# Impedance.net
KiCad netlist of a schematic drawn in EAGLE
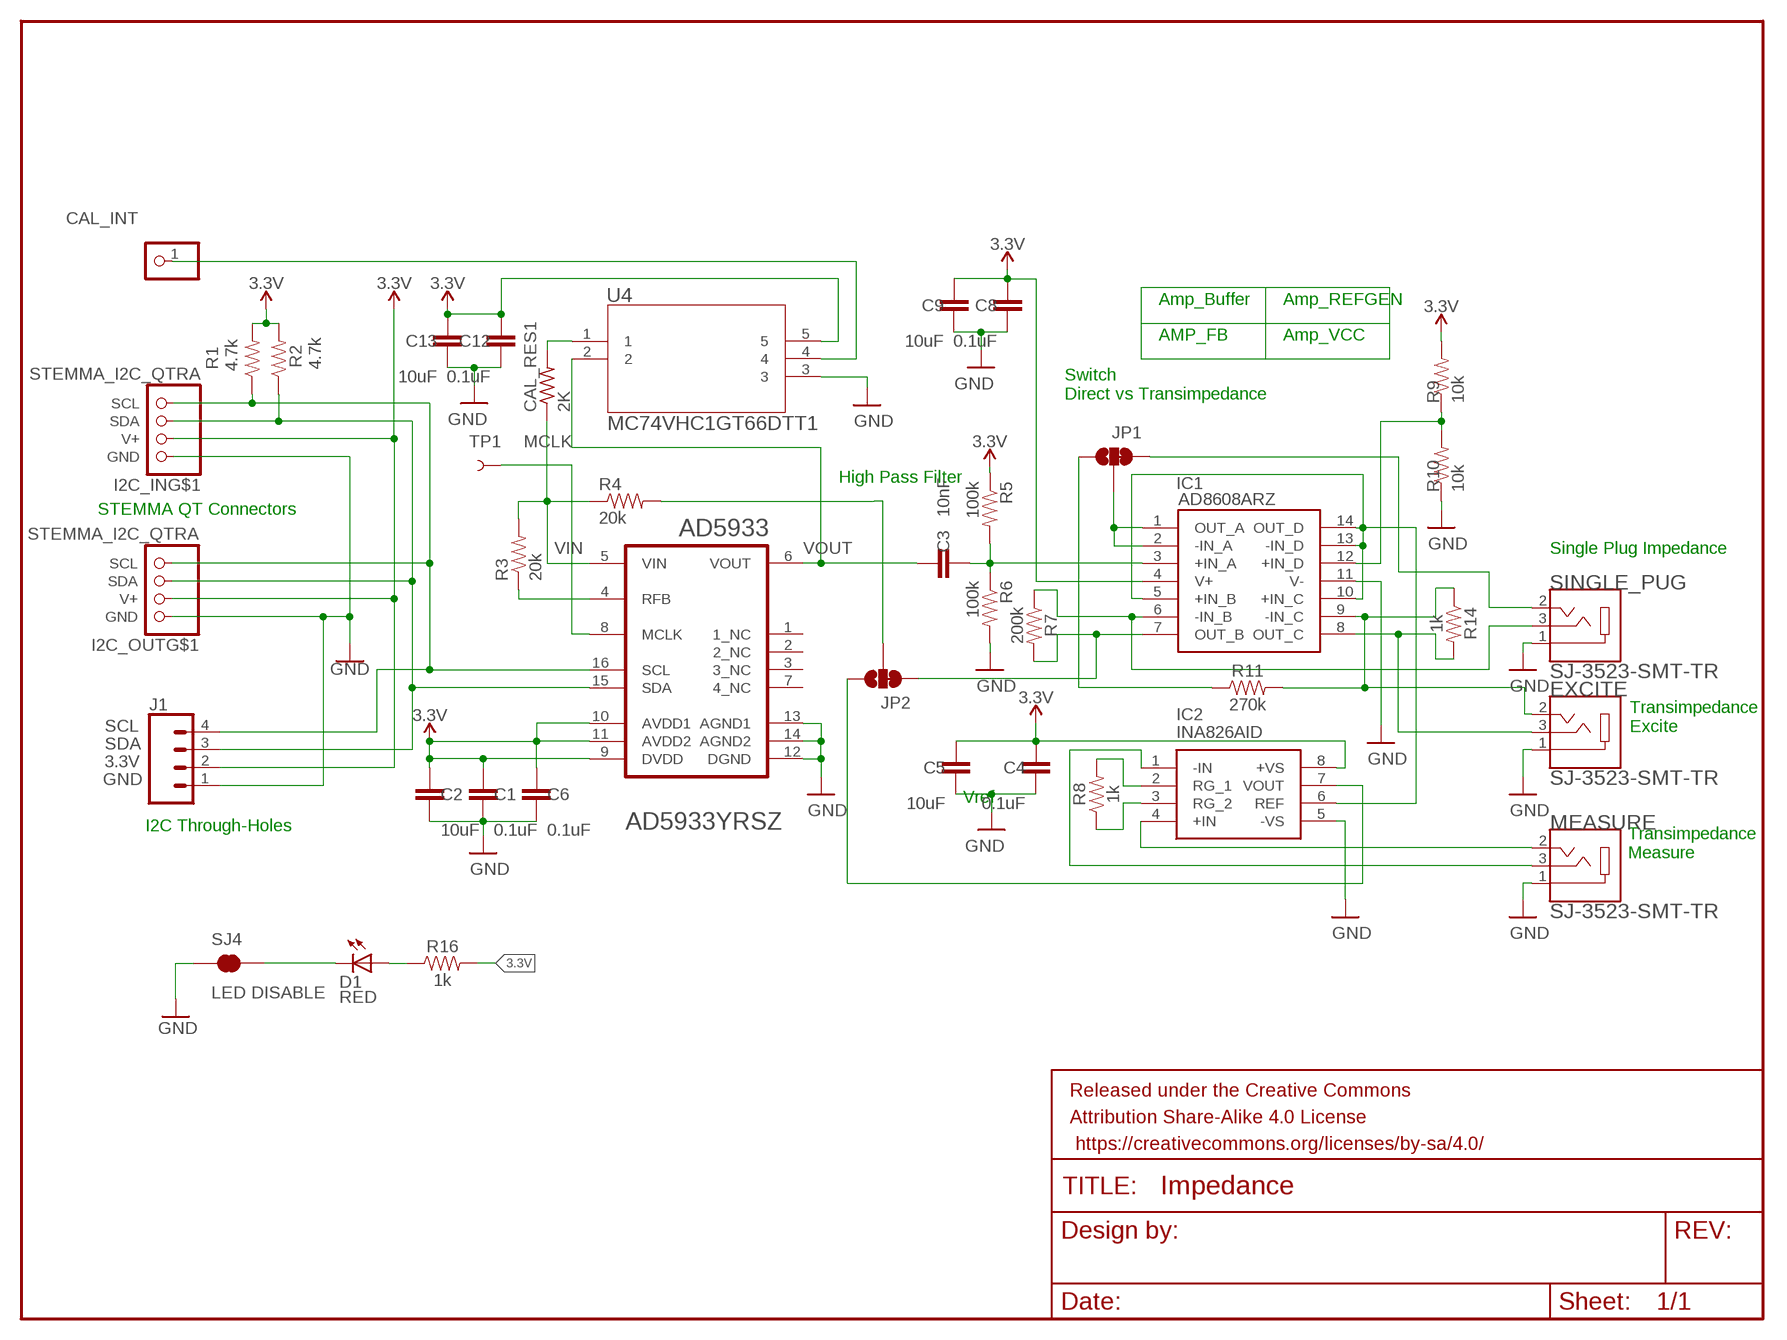
[diagram p0: schematic, sheet 1]

(export (version "E")
  (design (tool "Eeschema 10.0.6"))
  (components
    (comp (ref "AD5933")
      (value "ANALOG_DEVICES_AD5933YRSZANALOG_DEVICES_AD5933YRSZ_0_0")
      (footprint "eagle-import:ANALOG_DEVICES_AD5933YRSZ_0")
      (fields (field (name "MF") "Analog Devices") (field (name "MPN") "AD5933YRSZ"))
      (libsource (lib "eagle-import") (part "ANALOG_DEVICES_AD5933YRSZANALOG_DEVICES_AD5933YRSZ_0_0"))
    )
    (comp (ref "C1")
      (value "0.1uF")
      (footprint "eagle-import:0603")
      (libsource (lib "eagle-import") (part "0.1UF-0603-25V-(+80/-20%)"))
    )
    (comp (ref "C2")
      (value "10uF")
      (footprint "eagle-import:0603")
      (libsource (lib "eagle-import") (part "10UF-0603-6.3V-20%"))
    )
    (comp (ref "C3")
      (value "10nF")
      (footprint "eagle-import:0603")
      (libsource (lib "eagle-import") (part "10NF-0603-50V-10%"))
    )
    (comp (ref "C4")
      (value "0.1uF")
      (footprint "eagle-import:0603")
      (libsource (lib "eagle-import") (part "0.1UF-0603-25V-5%"))
    )
    (comp (ref "C5")
      (value "10uF")
      (footprint "eagle-import:0603")
      (libsource (lib "eagle-import") (part "10UF-0603-6.3V-20%"))
    )
    (comp (ref "C6")
      (value "0.1uF")
      (footprint "eagle-import:0603")
      (libsource (lib "eagle-import") (part "0.1UF-0603-25V-(+80/-20%)"))
    )
    (comp (ref "C8")
      (value "0.1uF")
      (footprint "eagle-import:0603")
      (libsource (lib "eagle-import") (part "0.1UF-0603-25V-5%"))
    )
    (comp (ref "C9")
      (value "10uF")
      (footprint "eagle-import:0603")
      (libsource (lib "eagle-import") (part "10UF-0603-6.3V-20%"))
    )
    (comp (ref "C12")
      (value "0.1uF")
      (footprint "eagle-import:0603")
      (libsource (lib "eagle-import") (part "0.1UF-0603-25V-5%"))
    )
    (comp (ref "C13")
      (value "10uF")
      (footprint "eagle-import:0603")
      (libsource (lib "eagle-import") (part "10UF-0603-6.3V-20%"))
    )
    (comp (ref "CAL_INT")
      (value "PINHD-1X1")
      (footprint "eagle-import:1X01")
      (libsource (lib "eagle-import") (part "PINHD-1X1"))
    )
    (comp (ref "CAL_RES1")
      (value "2K")
      (footprint "eagle-import:R0603")
      (libsource (lib "eagle-import") (part "R-US_R0603"))
    )
    (comp (ref "D1")
      (value "RED")
      (footprint "eagle-import:LED-0603")
      (libsource (lib "eagle-import") (part "LED-RED0603"))
    )
    (comp (ref "EXCITE")
      (value "SJ-3523-SMT-TR")
      (footprint "eagle-import:CUI_SJ-3523-SMT-TR")
      (fields (field (name "MF") "CUI Devices"))
      (libsource (lib "eagle-import") (part "SJ-3523-SMT-TR"))
    )
    (comp (ref "FRAME1")
      (value "FRAME-LETTERNO_PACKAGE")
      (footprint "eagle-import:DUMMY")
      (fields (field (name "DESIGNER") "Nobody"))
      (libsource (lib "eagle-import") (part "FRAME-LETTERNO_PACKAGE"))
    )
    (comp (ref "I2C_IN")
      (value "STEMMA_I2C_QTRA")
      (footprint "eagle-import:JST_SH4_RA")
      (libsource (lib "eagle-import") (part "STEMMA_I2C_QTRA"))
    )
    (comp (ref "I2C_OUT")
      (value "STEMMA_I2C_QTRA")
      (footprint "eagle-import:JST_SH4_RA")
      (libsource (lib "eagle-import") (part "STEMMA_I2C_QTRA"))
    )
    (comp (ref "IC1")
      (value "AD8608ARZ")
      (footprint "eagle-import:SOIC127P600X175-14N")
      (fields (field (name "MOUSER_PART_NUMBER") "584-AD8608ARZ"))
      (libsource (lib "eagle-import") (part "AD8608ARZ"))
    )
    (comp (ref "IC2")
      (value "INA826AID")
      (footprint "eagle-import:SOIC127P600X175-8N")
      (fields (field (name "MOUSER_PART_NUMBER") "595-INA826AID"))
      (libsource (lib "eagle-import") (part "INA826AID"))
    )
    (comp (ref "J1")
      (value "CONN_04")
      (footprint "eagle-import:1X04")
      (libsource (lib "eagle-import") (part "CONN_04"))
    )
    (comp (ref "JP1")
      (value "JUMPER-SMT_3_1-NC_TRACE_NO-SILK")
      (footprint "eagle-import:SMT-JUMPER_3_1-NC_TRACE_NO-SILK")
      (libsource (lib "eagle-import") (part "JUMPER-SMT_3_1-NC_TRACE_NO-SILK"))
    )
    (comp (ref "JP2")
      (value "JUMPER-SMT_3_1-NC_TRACE_NO-SILK")
      (footprint "eagle-import:SMT-JUMPER_3_1-NC_TRACE_NO-SILK")
      (libsource (lib "eagle-import") (part "JUMPER-SMT_3_1-NC_TRACE_NO-SILK"))
    )
    (comp (ref "MEASURE")
      (value "SJ-3523-SMT-TR")
      (footprint "eagle-import:CUI_SJ-3523-SMT-TR")
      (fields (field (name "MF") "CUI Devices"))
      (libsource (lib "eagle-import") (part "SJ-3523-SMT-TR"))
    )
    (comp (ref "R1")
      (value "4.7k")
      (footprint "eagle-import:0603")
      (libsource (lib "eagle-import") (part "4.7KOHM-0603-1/10W-1%"))
    )
    (comp (ref "R2")
      (value "4.7k")
      (footprint "eagle-import:0603")
      (libsource (lib "eagle-import") (part "4.7KOHM-0603-1/10W-1%"))
    )
    (comp (ref "R3")
      (value "20k")
      (footprint "eagle-import:0603")
      (libsource (lib "eagle-import") (part "20KOHM-0603-1/10W-1%"))
    )
    (comp (ref "R4")
      (value "20k")
      (footprint "eagle-import:0603")
      (libsource (lib "eagle-import") (part "20KOHM-0603-1/10W-1%"))
    )
    (comp (ref "R5")
      (value "100k")
      (footprint "eagle-import:0603")
      (libsource (lib "eagle-import") (part "100KOHM-0603-1/10W-1%"))
    )
    (comp (ref "R6")
      (value "100k")
      (footprint "eagle-import:0603")
      (libsource (lib "eagle-import") (part "100KOHM-0603-1/10W-1%"))
    )
    (comp (ref "R7")
      (value "200k")
      (footprint "eagle-import:0603")
      (libsource (lib "eagle-import") (part "200KOHM-0603-1/10W-1%"))
    )
    (comp (ref "R8")
      (value "1k")
      (footprint "eagle-import:0603")
      (libsource (lib "eagle-import") (part "1KOHM-0603-1/10W-1%"))
    )
    (comp (ref "R9")
      (value "10k")
      (footprint "eagle-import:0603")
      (libsource (lib "eagle-import") (part "10KOHM-0603-1/10W-1%"))
    )
    (comp (ref "R10")
      (value "10k")
      (footprint "eagle-import:0603")
      (libsource (lib "eagle-import") (part "10KOHM-0603-1/10W-1%"))
    )
    (comp (ref "R11")
      (value "270k")
      (footprint "eagle-import:0603")
      (libsource (lib "eagle-import") (part "220KOHM-0603-1/10W-1%"))
    )
    (comp (ref "R14")
      (value "1k")
      (footprint "eagle-import:0603")
      (libsource (lib "eagle-import") (part "1KOHM-0603-1/10W-1%"))
    )
    (comp (ref "R16")
      (value "1k")
      (footprint "eagle-import:0603")
      (libsource (lib "eagle-import") (part "1KOHM-0603-1/10W-1%"))
    )
    (comp (ref "SINGLE_PUG")
      (value "SJ-3523-SMT-TR")
      (footprint "eagle-import:CUI_SJ-3523-SMT-TR")
      (fields (field (name "MF") "CUI Devices"))
      (libsource (lib "eagle-import") (part "SJ-3523-SMT-TR"))
    )
    (comp (ref "SJ4")
      (value "LED DISABLE")
      (footprint "eagle-import:SMT-JUMPER_2_NC_TRACE_SILK")
      (libsource (lib "eagle-import") (part "JUMPER-SMT_2_NC_TRACE_SILK"))
    )
    (comp (ref "TP1")
      (value "TEST-POINT3X5")
      (footprint "eagle-import:PAD.03X.05")
      (libsource (lib "eagle-import") (part "TEST-POINT3X5"))
    )
    (comp (ref "U4")
      (value "MC74VHC1GT66DTT1")
      (footprint "eagle-import:TSOP5_1P65X3P15_ONS")
      (fields (field (name "COPYRIGHT") "Copyright (C) 2024 Ultra Librarian. All rights reserved."))
      (libsource (lib "eagle-import") (part "MC74VHC1GT66DTT1"))
    )
  )
  (nets
    (net (code "1") (name "/MCLK") (class "Default")
      (node (ref "AD5933") (pin "8") (pinfunction "MCLK_8") (pintype "input"))
      (node (ref "TP1") (pin "P$1") (pinfunction "1_P$1") (pintype "bidirectional"))
    )
    (net (code "2") (name "/SCL") (class "Default")
      (node (ref "AD5933") (pin "16") (pinfunction "SCL_16") (pintype "input"))
      (node (ref "I2C_IN") (pin "4") (pinfunction "SCL_4") (pintype "passive"))
      (node (ref "I2C_OUT") (pin "4") (pinfunction "SCL_4") (pintype "passive"))
      (node (ref "J1") (pin "4") (pinfunction "4_4") (pintype "passive"))
      (node (ref "R1") (pin "1") (pinfunction "1_1") (pintype "passive"))
    )
    (net (code "3") (name "/SDA") (class "Default")
      (node (ref "AD5933") (pin "15") (pinfunction "SDA_15") (pintype "bidirectional"))
      (node (ref "I2C_IN") (pin "3") (pinfunction "SDA_3") (pintype "passive"))
      (node (ref "I2C_OUT") (pin "3") (pinfunction "SDA_3") (pintype "passive"))
      (node (ref "J1") (pin "3") (pinfunction "3_3") (pintype "passive"))
      (node (ref "R2") (pin "1") (pinfunction "1_1") (pintype "passive"))
    )
    (net (code "4") (name "/VIN") (class "Default")
      (node (ref "AD5933") (pin "5") (pinfunction "VIN_5") (pintype "input"))
      (node (ref "CAL_RES1") (pin "1") (pinfunction "1_1") (pintype "passive"))
      (node (ref "R3") (pin "2") (pinfunction "2_2") (pintype "passive"))
      (node (ref "R4") (pin "1") (pinfunction "1_1") (pintype "passive"))
    )
    (net (code "5") (name "/VOUT") (class "Default")
      (node (ref "AD5933") (pin "6") (pinfunction "VOUT_6") (pintype "output"))
      (node (ref "C3") (pin "1") (pinfunction "1_1") (pintype "passive"))
      (node (ref "U4") (pin "2") (pinfunction "2_2") (pintype "passive"))
    )
    (net (code "6") (name "3.3V") (class "Default")
      (node (ref "AD5933") (pin "10") (pinfunction "AVDD1_10") (pintype "power_in"))
      (node (ref "AD5933") (pin "11") (pinfunction "AVDD2_11") (pintype "power_in"))
      (node (ref "AD5933") (pin "9") (pinfunction "DVDD_9") (pintype "power_in"))
      (node (ref "C1") (pin "1") (pinfunction "1_1") (pintype "passive"))
      (node (ref "C12") (pin "1") (pinfunction "1_1") (pintype "passive"))
      (node (ref "C13") (pin "1") (pinfunction "1_1") (pintype "passive"))
      (node (ref "C2") (pin "1") (pinfunction "1_1") (pintype "passive"))
      (node (ref "C4") (pin "1") (pinfunction "1_1") (pintype "passive"))
      (node (ref "C5") (pin "1") (pinfunction "1_1") (pintype "passive"))
      (node (ref "C6") (pin "1") (pinfunction "1_1") (pintype "passive"))
      (node (ref "C8") (pin "1") (pinfunction "1_1") (pintype "passive"))
      (node (ref "C9") (pin "1") (pinfunction "1_1") (pintype "passive"))
      (node (ref "I2C_IN") (pin "2") (pinfunction "V+_2") (pintype "passive"))
      (node (ref "I2C_OUT") (pin "2") (pinfunction "V+_2") (pintype "passive"))
      (node (ref "IC1") (pin "4") (pinfunction "V+_4") (pintype "power_in"))
      (node (ref "IC2") (pin "8") (pinfunction "+VS_8") (pintype "bidirectional"))
      (node (ref "J1") (pin "2") (pinfunction "2_2") (pintype "passive"))
      (node (ref "R1") (pin "2") (pinfunction "2_2") (pintype "passive"))
      (node (ref "R16") (pin "2") (pinfunction "2_2") (pintype "passive"))
      (node (ref "R2") (pin "2") (pinfunction "2_2") (pintype "passive"))
      (node (ref "R5") (pin "1") (pinfunction "1_1") (pintype "passive"))
      (node (ref "R9") (pin "2") (pinfunction "2_2") (pintype "passive"))
      (node (ref "U4") (pin "5") (pinfunction "5_5") (pintype "passive"))
    )
    (net (code "7") (name "GND") (class "Default")
      (node (ref "AD5933") (pin "12") (pinfunction "DGND_12") (pintype "power_in"))
      (node (ref "AD5933") (pin "13") (pinfunction "AGND1_13") (pintype "power_in"))
      (node (ref "AD5933") (pin "14") (pinfunction "AGND2_14") (pintype "power_in"))
      (node (ref "C1") (pin "2") (pinfunction "2_2") (pintype "passive"))
      (node (ref "C12") (pin "2") (pinfunction "2_2") (pintype "passive"))
      (node (ref "C13") (pin "2") (pinfunction "2_2") (pintype "passive"))
      (node (ref "C2") (pin "2") (pinfunction "2_2") (pintype "passive"))
      (node (ref "C4") (pin "2") (pinfunction "2_2") (pintype "passive"))
      (node (ref "C5") (pin "2") (pinfunction "2_2") (pintype "passive"))
      (node (ref "C6") (pin "2") (pinfunction "2_2") (pintype "passive"))
      (node (ref "C8") (pin "2") (pinfunction "2_2") (pintype "passive"))
      (node (ref "C9") (pin "2") (pinfunction "2_2") (pintype "passive"))
      (node (ref "EXCITE") (pin "1") (pinfunction "1_1") (pintype "passive"))
      (node (ref "I2C_IN") (pin "1") (pinfunction "GND_1") (pintype "passive"))
      (node (ref "I2C_OUT") (pin "1") (pinfunction "GND_1") (pintype "passive"))
      (node (ref "IC1") (pin "11") (pinfunction "V-_11") (pintype "power_in"))
      (node (ref "IC2") (pin "5") (pinfunction "-VS_5") (pintype "bidirectional"))
      (node (ref "J1") (pin "1") (pinfunction "1_1") (pintype "passive"))
      (node (ref "MEASURE") (pin "1") (pinfunction "1_1") (pintype "passive"))
      (node (ref "R10") (pin "1") (pinfunction "1_1") (pintype "passive"))
      (node (ref "R6") (pin "2") (pinfunction "2_2") (pintype "passive"))
      (node (ref "SINGLE_PUG") (pin "1") (pinfunction "1_1") (pintype "passive"))
      (node (ref "SJ4") (pin "1") (pinfunction "1_1") (pintype "passive"))
      (node (ref "U4") (pin "3") (pinfunction "3_3") (pintype "passive"))
    )
    (net (code "8") (name "Net-(AD5933-RFB)") (class "Default")
      (node (ref "AD5933") (pin "4") (pinfunction "RFB_4") (pintype "input"))
      (node (ref "R3") (pin "1") (pinfunction "1_1") (pintype "passive"))
    )
    (net (code "9") (name "Net-(CAL_INT-Pad1)") (class "Default")
      (node (ref "CAL_INT") (pin "1") (pinfunction "1_1") (pintype "passive"))
      (node (ref "U4") (pin "4") (pinfunction "4_4") (pintype "passive"))
    )
    (net (code "10") (name "Net-(CAL_RES1-Pad2)") (class "Default")
      (node (ref "CAL_RES1") (pin "2") (pinfunction "2_2") (pintype "passive"))
      (node (ref "U4") (pin "1") (pinfunction "1_1") (pintype "passive"))
    )
    (net (code "11") (name "Net-(D1-PadA)") (class "Default")
      (node (ref "D1") (pin "A") (pinfunction "A_A") (pintype "passive"))
      (node (ref "R16") (pin "1") (pinfunction "1_1") (pintype "passive"))
    )
    (net (code "12") (name "Net-(D1-PadC)") (class "Default")
      (node (ref "D1") (pin "C") (pinfunction "C_C") (pintype "passive"))
      (node (ref "SJ4") (pin "2") (pinfunction "2_2") (pintype "passive"))
    )
    (net (code "13") (name "Net-(IC1-+IN_A)") (class "Default")
      (node (ref "C3") (pin "2") (pinfunction "2_2") (pintype "passive"))
      (node (ref "IC1") (pin "3") (pinfunction "+IN_A_3") (pintype "input"))
      (node (ref "R5") (pin "2") (pinfunction "2_2") (pintype "passive"))
      (node (ref "R6") (pin "1") (pinfunction "1_1") (pintype "passive"))
    )
    (net (code "14") (name "Net-(IC1-+IN_B)") (class "Default")
      (node (ref "IC1") (pin "10") (pinfunction "+IN_C_10") (pintype "input"))
      (node (ref "IC1") (pin "13") (pinfunction "-IN_D_13") (pintype "input"))
      (node (ref "IC1") (pin "14") (pinfunction "OUT_D_14") (pintype "output"))
      (node (ref "IC1") (pin "5") (pinfunction "+IN_B_5") (pintype "input"))
      (node (ref "IC2") (pin "6") (pinfunction "REF_6") (pintype "bidirectional"))
    )
    (net (code "15") (name "Net-(IC1-+IN_D)") (class "Default")
      (node (ref "IC1") (pin "12") (pinfunction "+IN_D_12") (pintype "input"))
      (node (ref "R10") (pin "2") (pinfunction "2_2") (pintype "passive"))
      (node (ref "R9") (pin "1") (pinfunction "1_1") (pintype "passive"))
    )
    (net (code "16") (name "Net-(IC1--IN_A)") (class "Default")
      (node (ref "IC1") (pin "1") (pinfunction "OUT_A_1") (pintype "output"))
      (node (ref "IC1") (pin "2") (pinfunction "-IN_A_2") (pintype "input"))
      (node (ref "JP1") (pin "2") (pinfunction "2_2") (pintype "passive"))
    )
    (net (code "17") (name "Net-(IC1--IN_B)") (class "Default")
      (node (ref "IC1") (pin "6") (pinfunction "-IN_B_6") (pintype "input"))
      (node (ref "R7") (pin "1") (pinfunction "1_1") (pintype "passive"))
      (node (ref "SINGLE_PUG") (pin "3") (pinfunction "3_3") (pintype "passive"))
    )
    (net (code "18") (name "Net-(IC1--IN_C)") (class "Default")
      (node (ref "EXCITE") (pin "2") (pinfunction "2_2") (pintype "passive"))
      (node (ref "IC1") (pin "9") (pinfunction "-IN_C_9") (pintype "input"))
      (node (ref "R11") (pin "2") (pinfunction "2_2") (pintype "passive"))
      (node (ref "R14") (pin "1") (pinfunction "1_1") (pintype "passive"))
    )
    (net (code "19") (name "Net-(IC1-OUT_B)") (class "Default")
      (node (ref "IC1") (pin "7") (pinfunction "OUT_B_7") (pintype "output"))
      (node (ref "JP2") (pin "3") (pinfunction "3_3") (pintype "passive"))
      (node (ref "R7") (pin "2") (pinfunction "2_2") (pintype "passive"))
    )
    (net (code "20") (name "Net-(IC1-OUT_C)") (class "Default")
      (node (ref "EXCITE") (pin "3") (pinfunction "3_3") (pintype "passive"))
      (node (ref "IC1") (pin "8") (pinfunction "OUT_C_8") (pintype "output"))
      (node (ref "R14") (pin "2") (pinfunction "2_2") (pintype "passive"))
    )
    (net (code "21") (name "Net-(IC2-+IN)") (class "Default")
      (node (ref "IC2") (pin "4") (pinfunction "+IN_4") (pintype "bidirectional"))
      (node (ref "MEASURE") (pin "2") (pinfunction "2_2") (pintype "passive"))
    )
    (net (code "22") (name "Net-(IC2--IN)") (class "Default")
      (node (ref "IC2") (pin "1") (pinfunction "-IN_1") (pintype "bidirectional"))
      (node (ref "MEASURE") (pin "3") (pinfunction "3_3") (pintype "passive"))
    )
    (net (code "23") (name "Net-(IC2-RG_1)") (class "Default")
      (node (ref "IC2") (pin "2") (pinfunction "RG_1_2") (pintype "bidirectional"))
      (node (ref "R8") (pin "2") (pinfunction "2_2") (pintype "passive"))
    )
    (net (code "24") (name "Net-(IC2-RG_2)") (class "Default")
      (node (ref "IC2") (pin "3") (pinfunction "RG_2_3") (pintype "bidirectional"))
      (node (ref "R8") (pin "1") (pinfunction "1_1") (pintype "passive"))
    )
    (net (code "25") (name "Net-(IC2-VOUT)") (class "Default")
      (node (ref "IC2") (pin "7") (pinfunction "VOUT_7") (pintype "bidirectional"))
      (node (ref "JP2") (pin "1") (pinfunction "1_1") (pintype "passive"))
    )
    (net (code "26") (name "Net-(JP1-Pad1)") (class "Default")
      (node (ref "JP1") (pin "1") (pinfunction "1_1") (pintype "passive"))
      (node (ref "R11") (pin "1") (pinfunction "1_1") (pintype "passive"))
    )
    (net (code "27") (name "Net-(JP1-Pad3)") (class "Default")
      (node (ref "JP1") (pin "3") (pinfunction "3_3") (pintype "passive"))
      (node (ref "SINGLE_PUG") (pin "2") (pinfunction "2_2") (pintype "passive"))
    )
    (net (code "28") (name "Net-(JP2-Pad2)") (class "Default")
      (node (ref "JP2") (pin "2") (pinfunction "2_2") (pintype "passive"))
      (node (ref "R4") (pin "2") (pinfunction "2_2") (pintype "passive"))
    )
    (net (code "29") (name "unconnected-(AD5933-1_NC-Pad1)") (class "Default")
      (node (ref "AD5933") (pin "1") (pinfunction "1_NC_1") (pintype "passive"))
    )
    (net (code "30") (name "unconnected-(AD5933-2_NC-Pad2)") (class "Default")
      (node (ref "AD5933") (pin "2") (pinfunction "2_NC_2") (pintype "passive"))
    )
    (net (code "31") (name "unconnected-(AD5933-3_NC-Pad3)") (class "Default")
      (node (ref "AD5933") (pin "3") (pinfunction "3_NC_3") (pintype "passive"))
    )
    (net (code "32") (name "unconnected-(AD5933-4_NC-Pad7)") (class "Default")
      (node (ref "AD5933") (pin "7") (pinfunction "4_NC_7") (pintype "passive"))
    )
  )
)
